# EFM32ZGUSB_H.net
KiCad netlist of a schematic drawn in EAGLE
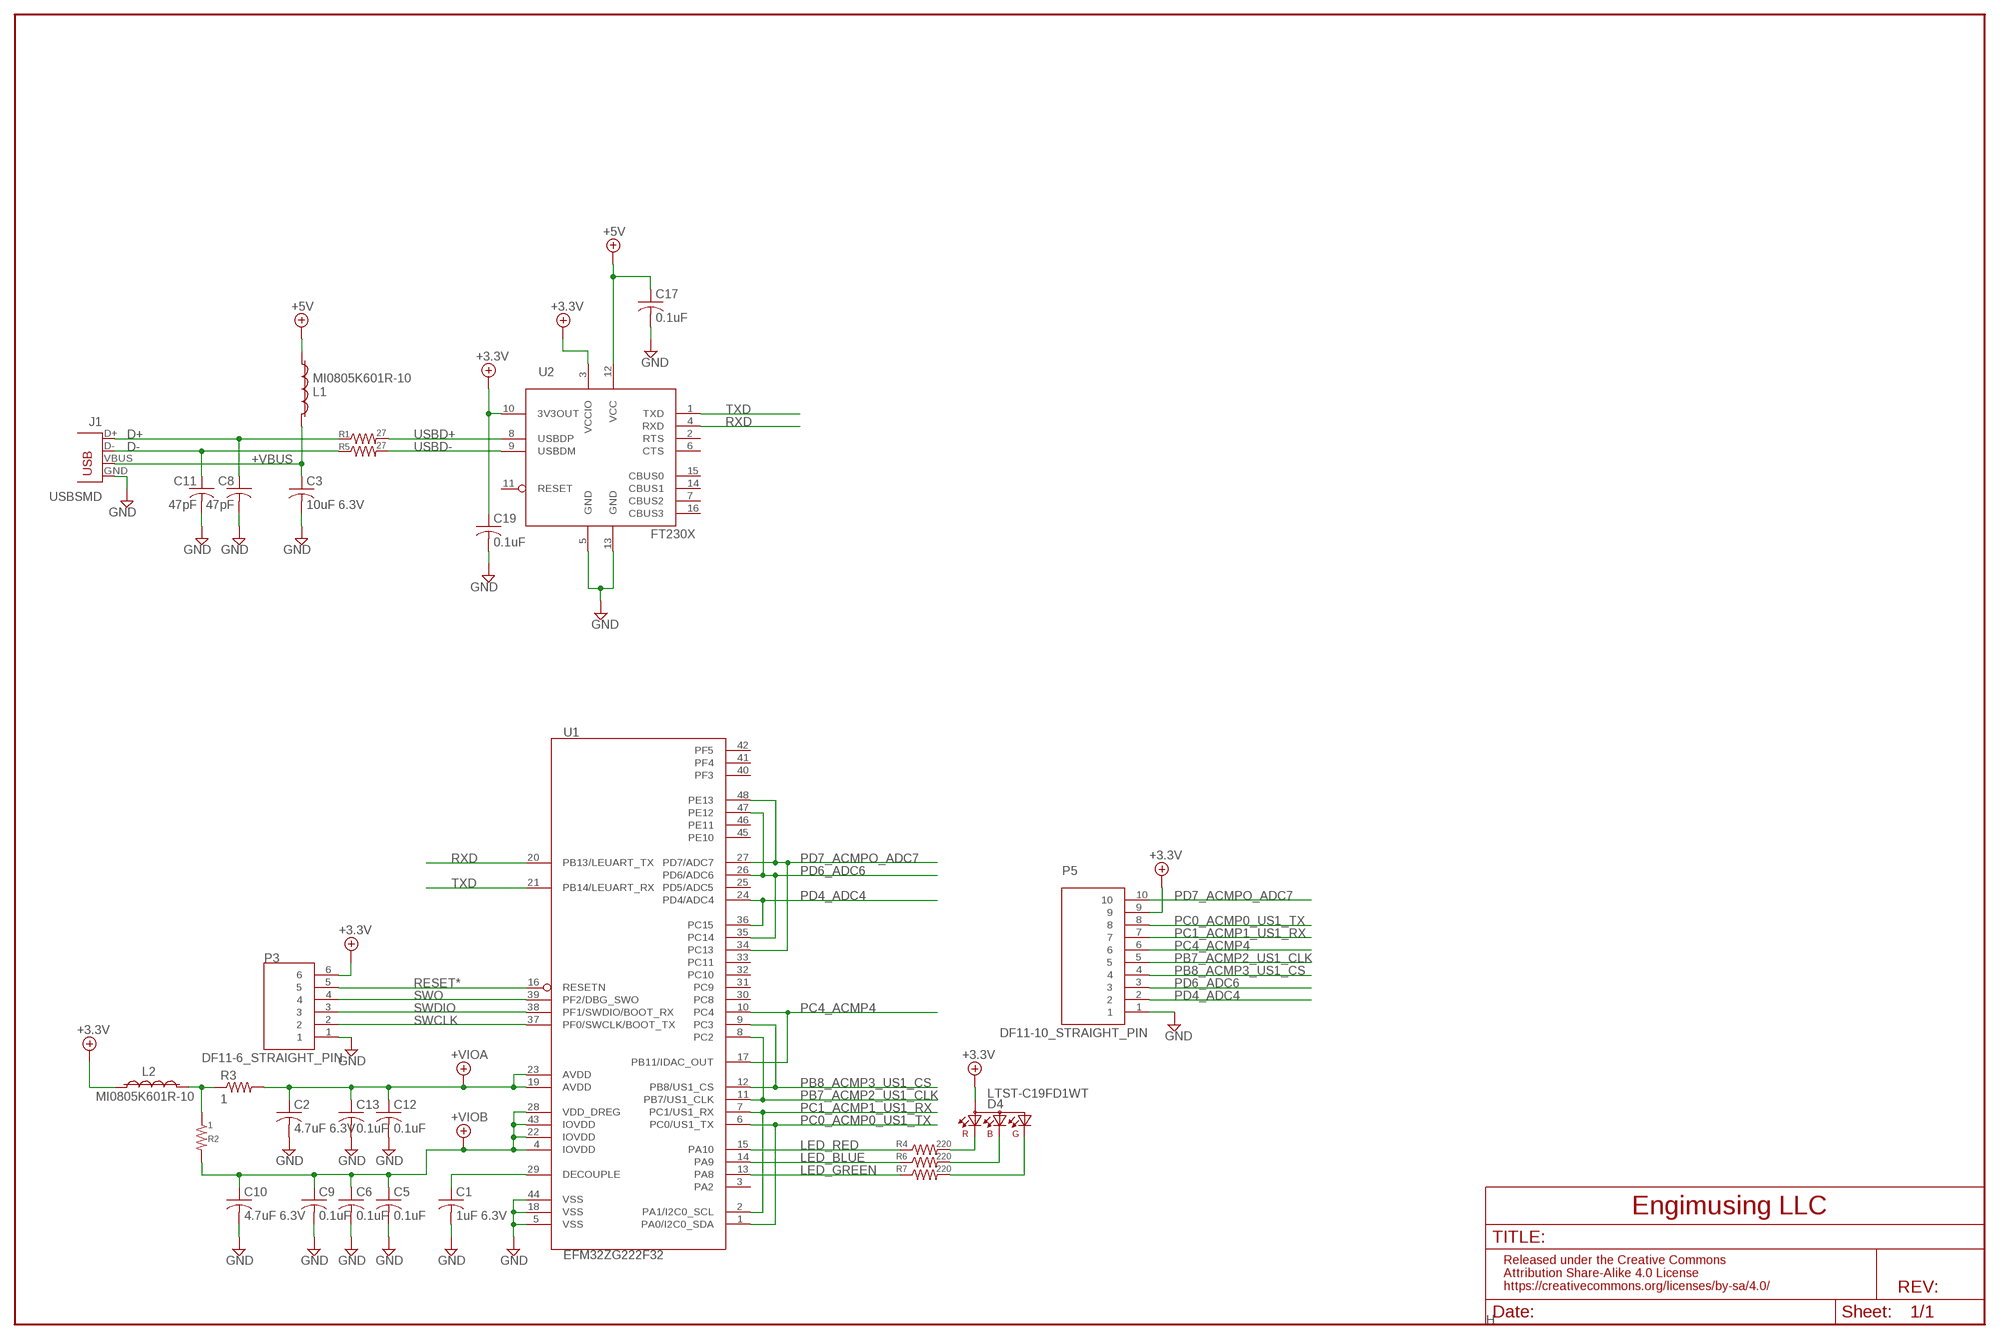
[diagram p0: schematic, sheet 1]

(export (version "E")
  (design (tool "Eeschema 10.0.6"))
  (components
    (comp (ref "C1")
      (value "1uF 6.3V")
      (footprint "eagle-import:C0603")
      (libsource (lib "eagle-import") (part "C-USC0603"))
    )
    (comp (ref "C2")
      (value "4.7uF 6.3V")
      (footprint "eagle-import:C0603")
      (libsource (lib "eagle-import") (part "C-USC0603"))
    )
    (comp (ref "C3")
      (value "10uF 6.3V")
      (footprint "eagle-import:C0603")
      (libsource (lib "eagle-import") (part "C-USC0603"))
    )
    (comp (ref "C5")
      (value "0.1uF")
      (footprint "eagle-import:C0402")
      (libsource (lib "eagle-import") (part "C-USC0402"))
    )
    (comp (ref "C6")
      (value "0.1uF")
      (footprint "eagle-import:C0402")
      (libsource (lib "eagle-import") (part "C-USC0402"))
    )
    (comp (ref "C8")
      (value "47pF")
      (footprint "eagle-import:C0603")
      (libsource (lib "eagle-import") (part "C-USC0603"))
    )
    (comp (ref "C9")
      (value "0.1uF")
      (footprint "eagle-import:C0402")
      (libsource (lib "eagle-import") (part "C-USC0402"))
    )
    (comp (ref "C10")
      (value "4.7uF 6.3V")
      (footprint "eagle-import:C0603")
      (libsource (lib "eagle-import") (part "C-USC0603"))
    )
    (comp (ref "C11")
      (value "47pF")
      (footprint "eagle-import:C0603")
      (libsource (lib "eagle-import") (part "C-USC0603"))
    )
    (comp (ref "C12")
      (value "0.1uF")
      (footprint "eagle-import:C0402")
      (libsource (lib "eagle-import") (part "C-USC0402"))
    )
    (comp (ref "C13")
      (value "0.1uF")
      (footprint "eagle-import:C0402")
      (libsource (lib "eagle-import") (part "C-USC0402"))
    )
    (comp (ref "C17")
      (value "0.1uF")
      (footprint "eagle-import:C0402")
      (libsource (lib "eagle-import") (part "C-USC0402"))
    )
    (comp (ref "C19")
      (value "0.1uF")
      (footprint "eagle-import:C0402")
      (libsource (lib "eagle-import") (part "C-USC0402"))
    )
    (comp (ref "D4")
      (value "LTST-C19FD1WT")
      (footprint "eagle-import:LED4")
      (libsource (lib "eagle-import") (part "LTST-C19FD1WT"))
    )
    (comp (ref "J1")
      (value "USBSMD")
      (footprint "eagle-import:USB-MINIB")
      (libsource (lib "eagle-import") (part "USBSMD"))
    )
    (comp (ref "L1")
      (value "MI0805K601R-10")
      (footprint "eagle-import:L0805_2.5")
      (libsource (lib "eagle-import") (part "FBEAD0805A"))
    )
    (comp (ref "L2")
      (value "MI0805K601R-10")
      (footprint "eagle-import:L0805_2.5")
      (libsource (lib "eagle-import") (part "FBEAD0805A"))
    )
    (comp (ref "P3")
      (value "DF11-6_STRAIGHT_PIN")
      (footprint "eagle-import:DF11SP-6-H")
      (libsource (lib "eagle-import") (part "DF11-6_STRAIGHT_PIN"))
    )
    (comp (ref "P5")
      (value "DF11-10_STRAIGHT_PIN")
      (footprint "eagle-import:DF11SP-10-H")
      (libsource (lib "eagle-import") (part "DF11-10_STRAIGHT_PIN"))
    )
    (comp (ref "R1")
      (value "27")
      (footprint "eagle-import:R0603")
      (libsource (lib "eagle-import") (part "R-USR0603"))
    )
    (comp (ref "R2")
      (value "1")
      (footprint "eagle-import:R0603")
      (libsource (lib "eagle-import") (part "R-USR0603"))
    )
    (comp (ref "R3")
      (value "1")
      (footprint "eagle-import:R0603")
      (libsource (lib "eagle-import") (part "R-USR0603"))
    )
    (comp (ref "R4")
      (value "220")
      (footprint "eagle-import:R0603")
      (libsource (lib "eagle-import") (part "R-USR0603"))
    )
    (comp (ref "R5")
      (value "27")
      (footprint "eagle-import:R0603")
      (libsource (lib "eagle-import") (part "R-USR0603"))
    )
    (comp (ref "R6")
      (value "220")
      (footprint "eagle-import:R0603")
      (libsource (lib "eagle-import") (part "R-USR0603"))
    )
    (comp (ref "R7")
      (value "220")
      (footprint "eagle-import:R0603")
      (libsource (lib "eagle-import") (part "R-USR0603"))
    )
    (comp (ref "U1")
      (value "EFM32ZG222F32")
      (footprint "eagle-import:QFP48")
      (libsource (lib "eagle-import") (part "EFM32ZG222F32"))
    )
    (comp (ref "U2")
      (value "FT230X")
      (footprint "eagle-import:SSOP16")
      (libsource (lib "eagle-import") (part "FT230X"))
    )
  )
  (nets
    (net (code "1") (name "+3.3V") (class "Default")
      (node (ref "C19") (pin "1") (pinfunction "1_1") (pintype "passive"))
      (node (ref "D4") (pin "A4") (pinfunction "A2_A4") (pintype "passive"))
      (node (ref "L2") (pin "1") (pinfunction "1_1") (pintype "passive"))
      (node (ref "P3") (pin "6") (pinfunction "6_6") (pintype "passive"))
      (node (ref "P5") (pin "9") (pinfunction "9_9") (pintype "passive"))
      (node (ref "U2") (pin "10") (pinfunction "3V3OUT_10") (pintype "bidirectional"))
      (node (ref "U2") (pin "3") (pinfunction "VCCIO_3") (pintype "bidirectional"))
    )
    (net (code "2") (name "+5V") (class "Default")
      (node (ref "C17") (pin "1") (pinfunction "1_1") (pintype "passive"))
      (node (ref "L1") (pin "1") (pinfunction "1_1") (pintype "passive"))
      (node (ref "U2") (pin "12") (pinfunction "VCC_12") (pintype "bidirectional"))
    )
    (net (code "3") (name "+VIOA") (class "Default")
      (node (ref "C12") (pin "1") (pinfunction "1_1") (pintype "passive"))
      (node (ref "C13") (pin "1") (pinfunction "1_1") (pintype "passive"))
      (node (ref "C2") (pin "1") (pinfunction "1_1") (pintype "passive"))
      (node (ref "R3") (pin "2") (pinfunction "2_2") (pintype "passive"))
      (node (ref "U1") (pin "19") (pinfunction "AVDD_19") (pintype "bidirectional"))
      (node (ref "U1") (pin "23") (pinfunction "AVDD_23") (pintype "bidirectional"))
    )
    (net (code "4") (name "+VIOB") (class "Default")
      (node (ref "C10") (pin "1") (pinfunction "1_1") (pintype "passive"))
      (node (ref "C5") (pin "1") (pinfunction "1_1") (pintype "passive"))
      (node (ref "C6") (pin "1") (pinfunction "1_1") (pintype "passive"))
      (node (ref "C9") (pin "1") (pinfunction "1_1") (pintype "passive"))
      (node (ref "R2") (pin "2") (pinfunction "2_2") (pintype "passive"))
      (node (ref "U1") (pin "22") (pinfunction "IOVDD_22") (pintype "bidirectional"))
      (node (ref "U1") (pin "28") (pinfunction "VDD_DREG_28") (pintype "bidirectional"))
      (node (ref "U1") (pin "4") (pinfunction "IOVDD_4") (pintype "bidirectional"))
      (node (ref "U1") (pin "43") (pinfunction "IOVDD_43") (pintype "bidirectional"))
    )
    (net (code "5") (name "/+VBUS") (class "Default")
      (node (ref "C3") (pin "1") (pinfunction "1_1") (pintype "passive"))
      (node (ref "J1") (pin "VBUS") (pinfunction "VBUS_VBUS") (pintype "bidirectional"))
      (node (ref "L1") (pin "2") (pinfunction "2_2") (pintype "passive"))
    )
    (net (code "6") (name "/D+") (class "Default")
      (node (ref "C8") (pin "1") (pinfunction "1_1") (pintype "passive"))
      (node (ref "J1") (pin "D+") (pinfunction "D+_D+") (pintype "bidirectional"))
      (node (ref "R1") (pin "1") (pinfunction "1_1") (pintype "passive"))
    )
    (net (code "7") (name "/D-") (class "Default")
      (node (ref "C11") (pin "1") (pinfunction "1_1") (pintype "passive"))
      (node (ref "J1") (pin "D-") (pinfunction "D-_D-") (pintype "bidirectional"))
      (node (ref "R5") (pin "1") (pinfunction "1_1") (pintype "passive"))
    )
    (net (code "8") (name "/LED_BLUE") (class "Default")
      (node (ref "R6") (pin "1") (pinfunction "1_1") (pintype "passive"))
      (node (ref "U1") (pin "14") (pinfunction "PA9_14") (pintype "bidirectional"))
    )
    (net (code "9") (name "/LED_GREEN") (class "Default")
      (node (ref "R7") (pin "1") (pinfunction "1_1") (pintype "passive"))
      (node (ref "U1") (pin "13") (pinfunction "PA8_13") (pintype "bidirectional"))
    )
    (net (code "10") (name "/LED_RED") (class "Default")
      (node (ref "R4") (pin "1") (pinfunction "1_1") (pintype "passive"))
      (node (ref "U1") (pin "15") (pinfunction "PA10_15") (pintype "bidirectional"))
    )
    (net (code "11") (name "/PB7_ACMP2_US1_CLK") (class "Default")
      (node (ref "P5") (pin "5") (pinfunction "5_5") (pintype "passive"))
      (node (ref "U1") (pin "11") (pinfunction "PB7/US1_CLK_11") (pintype "bidirectional"))
      (node (ref "U1") (pin "8") (pinfunction "PC2_8") (pintype "bidirectional"))
    )
    (net (code "12") (name "/PB8_ACMP3_US1_CS") (class "Default")
      (node (ref "P5") (pin "4") (pinfunction "4_4") (pintype "passive"))
      (node (ref "U1") (pin "12") (pinfunction "PB8/US1_CS_12") (pintype "bidirectional"))
      (node (ref "U1") (pin "9") (pinfunction "PC3_9") (pintype "bidirectional"))
    )
    (net (code "13") (name "/PC0_ACMP0_US1_TX") (class "Default")
      (node (ref "P5") (pin "8") (pinfunction "8_8") (pintype "passive"))
      (node (ref "U1") (pin "1") (pinfunction "PA0/I2C0_SDA_1") (pintype "bidirectional"))
      (node (ref "U1") (pin "6") (pinfunction "PC0/US1_TX_6") (pintype "bidirectional"))
    )
    (net (code "14") (name "/PC1_ACMP1_US1_RX") (class "Default")
      (node (ref "P5") (pin "7") (pinfunction "7_7") (pintype "passive"))
      (node (ref "U1") (pin "2") (pinfunction "PA1/I2C0_SCL_2") (pintype "bidirectional"))
      (node (ref "U1") (pin "7") (pinfunction "PC1/US1_RX_7") (pintype "bidirectional"))
    )
    (net (code "15") (name "/PC4_ACMP4") (class "Default")
      (node (ref "P5") (pin "6") (pinfunction "6_6") (pintype "passive"))
      (node (ref "U1") (pin "10") (pinfunction "PC4_10") (pintype "bidirectional"))
      (node (ref "U1") (pin "17") (pinfunction "PB11/IDAC_OUT_17") (pintype "bidirectional"))
    )
    (net (code "16") (name "/PD4_ADC4") (class "Default")
      (node (ref "P5") (pin "2") (pinfunction "2_2") (pintype "passive"))
      (node (ref "U1") (pin "24") (pinfunction "PD4/ADC4_24") (pintype "bidirectional"))
      (node (ref "U1") (pin "36") (pinfunction "PC15_36") (pintype "bidirectional"))
    )
    (net (code "17") (name "/PD6_ADC6") (class "Default")
      (node (ref "P5") (pin "3") (pinfunction "3_3") (pintype "passive"))
      (node (ref "U1") (pin "26") (pinfunction "PD6/ADC6_26") (pintype "bidirectional"))
      (node (ref "U1") (pin "35") (pinfunction "PC14_35") (pintype "bidirectional"))
      (node (ref "U1") (pin "47") (pinfunction "PE12_47") (pintype "bidirectional"))
    )
    (net (code "18") (name "/PD7_ACMPO_ADC7") (class "Default")
      (node (ref "P5") (pin "10") (pinfunction "10_10") (pintype "passive"))
      (node (ref "U1") (pin "27") (pinfunction "PD7/ADC7_27") (pintype "bidirectional"))
      (node (ref "U1") (pin "34") (pinfunction "PC13_34") (pintype "bidirectional"))
      (node (ref "U1") (pin "48") (pinfunction "PE13_48") (pintype "bidirectional"))
    )
    (net (code "19") (name "/RESET*") (class "Default")
      (node (ref "P3") (pin "5") (pinfunction "5_5") (pintype "passive"))
      (node (ref "U1") (pin "16") (pinfunction "RESETN_16") (pintype "bidirectional"))
    )
    (net (code "20") (name "/RXD") (class "Default")
      (node (ref "U1") (pin "20") (pinfunction "PB13/LEUART_TX_20") (pintype "bidirectional"))
      (node (ref "U2") (pin "4") (pinfunction "RXD_4") (pintype "bidirectional"))
    )
    (net (code "21") (name "/SWCLK") (class "Default")
      (node (ref "P3") (pin "2") (pinfunction "2_2") (pintype "passive"))
      (node (ref "U1") (pin "37") (pinfunction "PF0/SWCLK/BOOT_TX_37") (pintype "bidirectional"))
    )
    (net (code "22") (name "/SWDIO") (class "Default")
      (node (ref "P3") (pin "3") (pinfunction "3_3") (pintype "passive"))
      (node (ref "U1") (pin "38") (pinfunction "PF1/SWDIO/BOOT_RX_38") (pintype "bidirectional"))
    )
    (net (code "23") (name "/SWO") (class "Default")
      (node (ref "P3") (pin "4") (pinfunction "4_4") (pintype "passive"))
      (node (ref "U1") (pin "39") (pinfunction "PF2/DBG_SWO_39") (pintype "bidirectional"))
    )
    (net (code "24") (name "/TXD") (class "Default")
      (node (ref "U1") (pin "21") (pinfunction "PB14/LEUART_RX_21") (pintype "bidirectional"))
      (node (ref "U2") (pin "1") (pinfunction "TXD_1") (pintype "bidirectional"))
    )
    (net (code "25") (name "/USBD+") (class "Default")
      (node (ref "R1") (pin "2") (pinfunction "2_2") (pintype "passive"))
      (node (ref "U2") (pin "8") (pinfunction "USBDP_8") (pintype "bidirectional"))
    )
    (net (code "26") (name "/USBD-") (class "Default")
      (node (ref "R5") (pin "2") (pinfunction "2_2") (pintype "passive"))
      (node (ref "U2") (pin "9") (pinfunction "USBDM_9") (pintype "bidirectional"))
    )
    (net (code "27") (name "GND") (class "Default")
      (node (ref "C1") (pin "2") (pinfunction "2_2") (pintype "passive"))
      (node (ref "C10") (pin "2") (pinfunction "2_2") (pintype "passive"))
      (node (ref "C11") (pin "2") (pinfunction "2_2") (pintype "passive"))
      (node (ref "C12") (pin "2") (pinfunction "2_2") (pintype "passive"))
      (node (ref "C13") (pin "2") (pinfunction "2_2") (pintype "passive"))
      (node (ref "C17") (pin "2") (pinfunction "2_2") (pintype "passive"))
      (node (ref "C19") (pin "2") (pinfunction "2_2") (pintype "passive"))
      (node (ref "C2") (pin "2") (pinfunction "2_2") (pintype "passive"))
      (node (ref "C3") (pin "2") (pinfunction "2_2") (pintype "passive"))
      (node (ref "C5") (pin "2") (pinfunction "2_2") (pintype "passive"))
      (node (ref "C6") (pin "2") (pinfunction "2_2") (pintype "passive"))
      (node (ref "C8") (pin "2") (pinfunction "2_2") (pintype "passive"))
      (node (ref "C9") (pin "2") (pinfunction "2_2") (pintype "passive"))
      (node (ref "J1") (pin "GND") (pinfunction "GND_GND") (pintype "bidirectional"))
      (node (ref "P3") (pin "1") (pinfunction "1_1") (pintype "passive"))
      (node (ref "P5") (pin "1") (pinfunction "1_1") (pintype "passive"))
      (node (ref "U1") (pin "18") (pinfunction "VSS_18") (pintype "bidirectional"))
      (node (ref "U1") (pin "44") (pinfunction "VSS_44") (pintype "bidirectional"))
      (node (ref "U1") (pin "5") (pinfunction "VSS_5") (pintype "bidirectional"))
      (node (ref "U2") (pin "13") (pinfunction "GND_13") (pintype "bidirectional"))
      (node (ref "U2") (pin "5") (pinfunction "GND_5") (pintype "bidirectional"))
    )
    (net (code "28") (name "Net-(D4-CBLUE)") (class "Default")
      (node (ref "D4") (pin "B1") (pinfunction "CBLUE_B1") (pintype "passive"))
      (node (ref "R6") (pin "2") (pinfunction "2_2") (pintype "passive"))
    )
    (net (code "29") (name "Net-(D4-CGREEN)") (class "Default")
      (node (ref "D4") (pin "G3") (pinfunction "CGREEN_G3") (pintype "passive"))
      (node (ref "R7") (pin "2") (pinfunction "2_2") (pintype "passive"))
    )
    (net (code "30") (name "Net-(D4-CRED)") (class "Default")
      (node (ref "D4") (pin "R2") (pinfunction "CRED_R2") (pintype "passive"))
      (node (ref "R4") (pin "2") (pinfunction "2_2") (pintype "passive"))
    )
    (net (code "31") (name "Net-(L2-Pad2)") (class "Default")
      (node (ref "L2") (pin "2") (pinfunction "2_2") (pintype "passive"))
      (node (ref "R2") (pin "1") (pinfunction "1_1") (pintype "passive"))
      (node (ref "R3") (pin "1") (pinfunction "1_1") (pintype "passive"))
    )
    (net (code "32") (name "Net-(U1-DECOUPLE)") (class "Default")
      (node (ref "C1") (pin "1") (pinfunction "1_1") (pintype "passive"))
      (node (ref "U1") (pin "29") (pinfunction "DECOUPLE_29") (pintype "bidirectional"))
    )
    (net (code "33") (name "unconnected-(U1-PA2-Pad3)") (class "Default")
      (node (ref "U1") (pin "3") (pinfunction "PA2_3") (pintype "bidirectional"))
    )
    (net (code "34") (name "unconnected-(U1-PC8-Pad30)") (class "Default")
      (node (ref "U1") (pin "30") (pinfunction "PC8_30") (pintype "bidirectional"))
    )
    (net (code "35") (name "unconnected-(U1-PC9-Pad31)") (class "Default")
      (node (ref "U1") (pin "31") (pinfunction "PC9_31") (pintype "bidirectional"))
    )
    (net (code "36") (name "unconnected-(U1-PC10-Pad32)") (class "Default")
      (node (ref "U1") (pin "32") (pinfunction "PC10_32") (pintype "bidirectional"))
    )
    (net (code "37") (name "unconnected-(U1-PC11-Pad33)") (class "Default")
      (node (ref "U1") (pin "33") (pinfunction "PC11_33") (pintype "bidirectional"))
    )
    (net (code "38") (name "unconnected-(U1-PD5{slash}ADC5-Pad25)") (class "Default")
      (node (ref "U1") (pin "25") (pinfunction "PD5/ADC5_25") (pintype "bidirectional"))
    )
    (net (code "39") (name "unconnected-(U1-PE10-Pad45)") (class "Default")
      (node (ref "U1") (pin "45") (pinfunction "PE10_45") (pintype "bidirectional"))
    )
    (net (code "40") (name "unconnected-(U1-PE11-Pad46)") (class "Default")
      (node (ref "U1") (pin "46") (pinfunction "PE11_46") (pintype "bidirectional"))
    )
    (net (code "41") (name "unconnected-(U1-PF3-Pad40)") (class "Default")
      (node (ref "U1") (pin "40") (pinfunction "PF3_40") (pintype "bidirectional"))
    )
    (net (code "42") (name "unconnected-(U1-PF4-Pad41)") (class "Default")
      (node (ref "U1") (pin "41") (pinfunction "PF4_41") (pintype "bidirectional"))
    )
    (net (code "43") (name "unconnected-(U1-PF5-Pad42)") (class "Default")
      (node (ref "U1") (pin "42") (pinfunction "PF5_42") (pintype "bidirectional"))
    )
    (net (code "44") (name "unconnected-(U2-CBUS0-Pad15)") (class "Default")
      (node (ref "U2") (pin "15") (pinfunction "CBUS0_15") (pintype "bidirectional"))
    )
    (net (code "45") (name "unconnected-(U2-CBUS1-Pad14)") (class "Default")
      (node (ref "U2") (pin "14") (pinfunction "CBUS1_14") (pintype "bidirectional"))
    )
    (net (code "46") (name "unconnected-(U2-CBUS2-Pad7)") (class "Default")
      (node (ref "U2") (pin "7") (pinfunction "CBUS2_7") (pintype "bidirectional"))
    )
    (net (code "47") (name "unconnected-(U2-CBUS3-Pad16)") (class "Default")
      (node (ref "U2") (pin "16") (pinfunction "CBUS3_16") (pintype "bidirectional"))
    )
    (net (code "48") (name "unconnected-(U2-CTS-Pad6)") (class "Default")
      (node (ref "U2") (pin "6") (pinfunction "CTS_6") (pintype "bidirectional"))
    )
    (net (code "49") (name "unconnected-(U2-RESET-Pad11)") (class "Default")
      (node (ref "U2") (pin "11") (pinfunction "RESET_11") (pintype "bidirectional"))
    )
    (net (code "50") (name "unconnected-(U2-RTS-Pad2)") (class "Default")
      (node (ref "U2") (pin "2") (pinfunction "RTS_2") (pintype "bidirectional"))
    )
  )
)
